# 2_mb_conn.net
KiCad netlist of a schematic drawn in Altium Designer
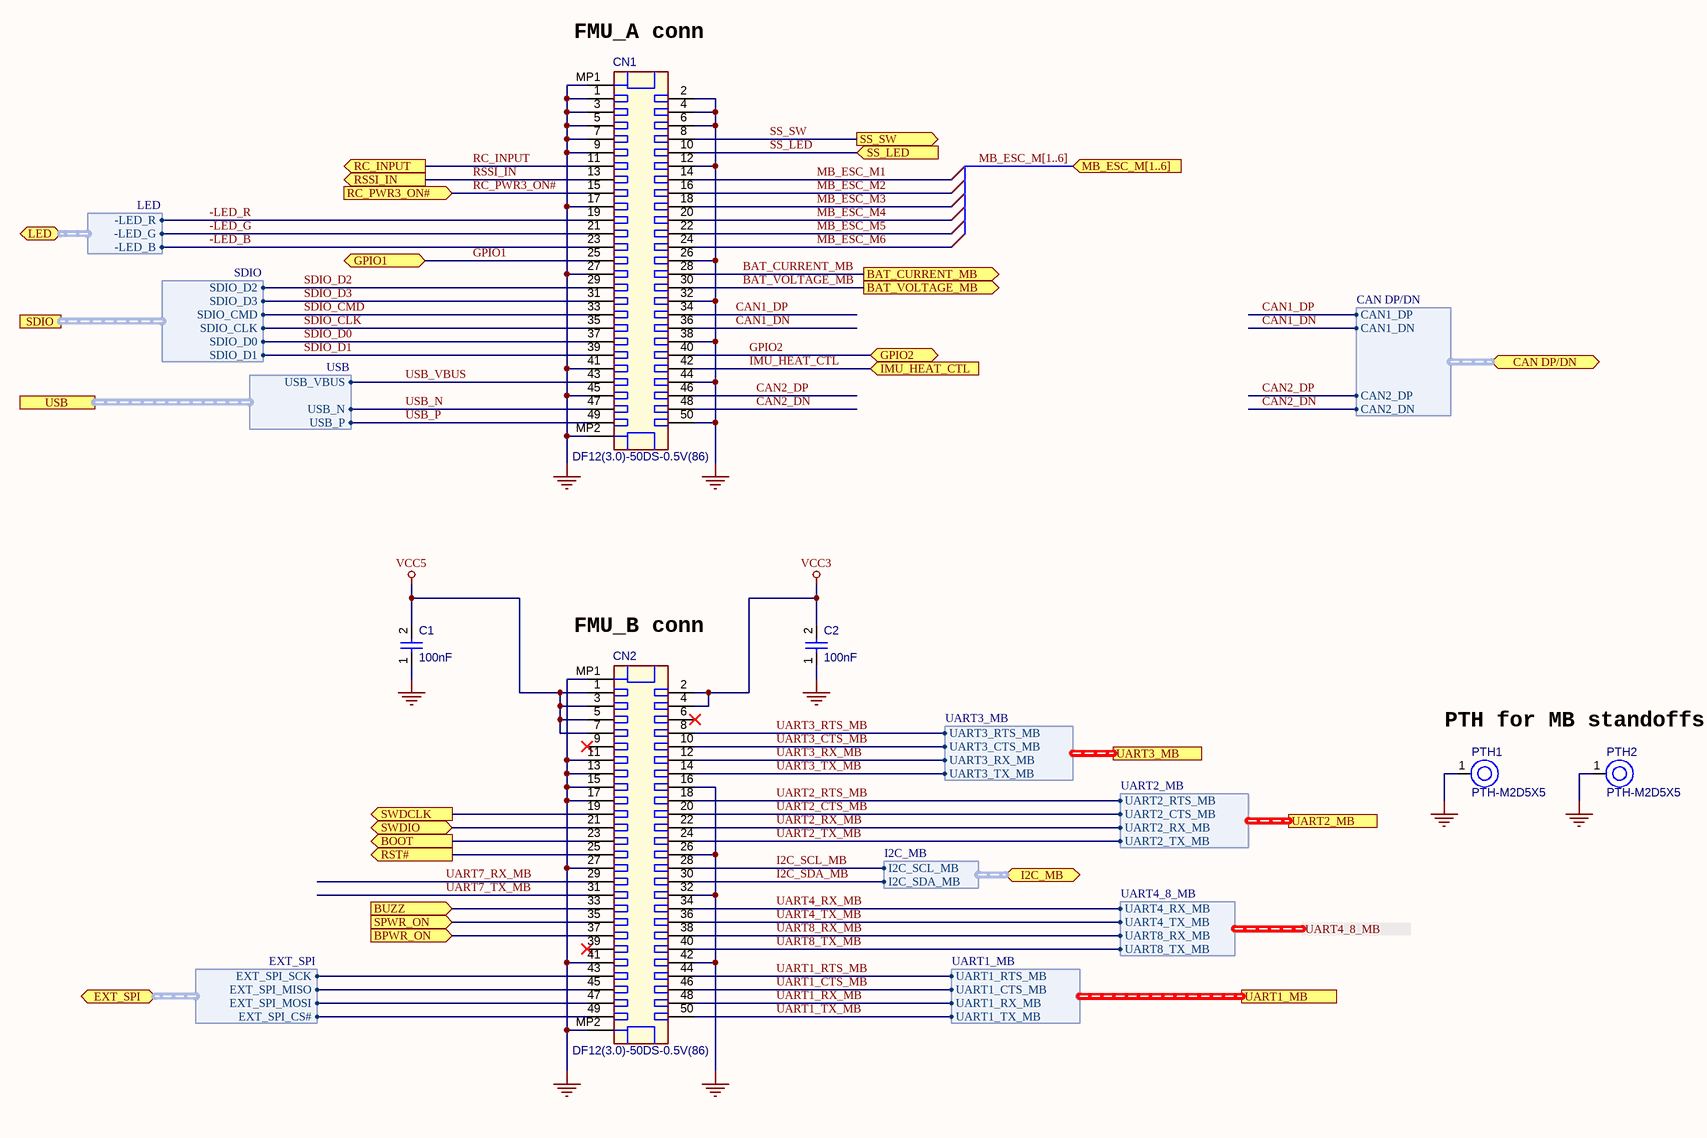
[diagram p0: 2_mb_conn.SchDoc]

(export (version "E")
  (design (tool "Eeschema 10.0.6"))
  (components
    (comp (ref "C1")
      (value "100nF")
      (footprint "CAPC0402(1005)60_L")
      (description "Chip Capacitor, 100nF +/-20%, 10V, 0402, Thickness 0.6 mm")
      (fields (field (name "TOLERANCE") "20%") (field (name "Comment") "Capacitor 100nF +/-20% 10V 0402"))
      (libsource (lib "<Company> Server") (part "CAP-NP-2"))
    )
    (comp (ref "C2")
      (value "100nF")
      (footprint "CAPC0402(1005)60_L")
      (description "Chip Capacitor, 100nF +/-20%, 10V, 0402, Thickness 0.6 mm")
      (fields (field (name "TOLERANCE") "20%") (field (name "Comment") "Capacitor 100nF +/-20% 10V 0402"))
      (libsource (lib "<Company> Server") (part "CAP-NP-2"))
    )
    (comp (ref "CN1")
      (value "DF12(3.0)-50DS-0.5V(86)")
      (footprint "HIRO-DF12(3.0)-50DS-0.5V_V")
      (description "Receptacle Connector, 50 V, 0.3 A, -45 to 125 degC, RoHS, Tape and Reel")
      (libsource (lib "<Company> Server") (part "CMP-00111-4"))
    )
    (comp (ref "CN2")
      (value "DF12(3.0)-50DS-0.5V(86)")
      (footprint "HIRO-DF12(3.0)-50DS-0.5V_V")
      (description "Receptacle Connector, 50 V, 0.3 A, -45 to 125 degC, RoHS, Tape and Reel")
      (libsource (lib "<Company> Server") (part "CMP-00111-4"))
    )
    (comp (ref "PTH1")
      (value "PTH-M2D5X5")
      (footprint "PTH-M2D5X5")
      (description "M2 PTH (2.5mm), 5mm pad")
      (libsource (lib "<Company> Server") (part "CMP-00028-00000-1"))
    )
    (comp (ref "PTH2")
      (value "PTH-M2D5X5")
      (footprint "PTH-M2D5X5")
      (description "M2 PTH (2.5mm), 5mm pad")
      (libsource (lib "<Company> Server") (part "CMP-00028-00000-1"))
    )
  )
  (nets
    (net (code "12") (name "/-LED_B") (class "Default")
      (node (ref "CN1") (pin "23") (pinfunction "23_23") (pintype "passive"))
    )
    (net (code "13") (name "/-LED_G") (class "Default")
      (node (ref "CN1") (pin "21") (pinfunction "21_21") (pintype "passive"))
    )
    (net (code "14") (name "/-LED_R") (class "Default")
      (node (ref "CN1") (pin "19") (pinfunction "19_19") (pintype "passive"))
    )
    (net (code "15") (name "/BAT_CURRENT_MB") (class "Default")
      (node (ref "CN1") (pin "28") (pinfunction "28_28") (pintype "passive"))
    )
    (net (code "16") (name "/BAT_VOLTAGE_MB") (class "Default")
      (node (ref "CN1") (pin "30") (pinfunction "30_30") (pintype "passive"))
    )
    (net (code "17") (name "/BOOT") (class "Default")
      (node (ref "CN2") (pin "23") (pinfunction "23_23") (pintype "passive"))
    )
    (net (code "18") (name "/BPWR_ON") (class "Default")
      (node (ref "CN2") (pin "37") (pinfunction "37_37") (pintype "passive"))
    )
    (net (code "19") (name "/BUZZ") (class "Default")
      (node (ref "CN2") (pin "33") (pinfunction "33_33") (pintype "passive"))
    )
    (net (code "20") (name "/CAN1_DN") (class "Default")
      (node (ref "CN1") (pin "36") (pinfunction "36_36") (pintype "passive"))
    )
    (net (code "21") (name "/CAN1_DP") (class "Default")
      (node (ref "CN1") (pin "34") (pinfunction "34_34") (pintype "passive"))
    )
    (net (code "22") (name "/CAN2_DN") (class "Default")
      (node (ref "CN1") (pin "48") (pinfunction "48_48") (pintype "passive"))
    )
    (net (code "23") (name "/CAN2_DP") (class "Default")
      (node (ref "CN1") (pin "46") (pinfunction "46_46") (pintype "passive"))
    )
    (net (code "24") (name "/EXT_SPI_CS#") (class "Default")
      (node (ref "CN2") (pin "49") (pinfunction "49_49") (pintype "passive"))
    )
    (net (code "25") (name "/EXT_SPI_MISO") (class "Default")
      (node (ref "CN2") (pin "45") (pinfunction "45_45") (pintype "passive"))
    )
    (net (code "26") (name "/EXT_SPI_MOSI") (class "Default")
      (node (ref "CN2") (pin "47") (pinfunction "47_47") (pintype "passive"))
    )
    (net (code "27") (name "/EXT_SPI_SCK") (class "Default")
      (node (ref "CN2") (pin "43") (pinfunction "43_43") (pintype "passive"))
    )
    (net (code "28") (name "/GPIO1") (class "Default")
      (node (ref "CN1") (pin "25") (pinfunction "25_25") (pintype "passive"))
    )
    (net (code "29") (name "/GPIO2") (class "Default")
      (node (ref "CN1") (pin "40") (pinfunction "40_40") (pintype "passive"))
    )
    (net (code "30") (name "/I2C_SCL_MB") (class "Default")
      (node (ref "CN2") (pin "28") (pinfunction "28_28") (pintype "passive"))
    )
    (net (code "31") (name "/I2C_SDA_MB") (class "Default")
      (node (ref "CN2") (pin "30") (pinfunction "30_30") (pintype "passive"))
    )
    (net (code "32") (name "/IMU_HEAT_CTL") (class "Default")
      (node (ref "CN1") (pin "42") (pinfunction "42_42") (pintype "passive"))
    )
    (net (code "33") (name "/MB_ESC_M1") (class "Default")
      (node (ref "CN1") (pin "14") (pinfunction "14_14") (pintype "passive"))
    )
    (net (code "34") (name "/MB_ESC_M2") (class "Default")
      (node (ref "CN1") (pin "16") (pinfunction "16_16") (pintype "passive"))
    )
    (net (code "35") (name "/MB_ESC_M3") (class "Default")
      (node (ref "CN1") (pin "18") (pinfunction "18_18") (pintype "passive"))
    )
    (net (code "36") (name "/MB_ESC_M4") (class "Default")
      (node (ref "CN1") (pin "20") (pinfunction "20_20") (pintype "passive"))
    )
    (net (code "37") (name "/MB_ESC_M5") (class "Default")
      (node (ref "CN1") (pin "22") (pinfunction "22_22") (pintype "passive"))
    )
    (net (code "38") (name "/MB_ESC_M6") (class "Default")
      (node (ref "CN1") (pin "24") (pinfunction "24_24") (pintype "passive"))
    )
    (net (code "40") (name "/RC_INPUT") (class "Default")
      (node (ref "CN1") (pin "11") (pinfunction "11_11") (pintype "passive"))
    )
    (net (code "41") (name "/RC_PWR3_ON#") (class "Default")
      (node (ref "CN1") (pin "15") (pinfunction "15_15") (pintype "passive"))
    )
    (net (code "42") (name "/RSSI_IN") (class "Default")
      (node (ref "CN1") (pin "13") (pinfunction "13_13") (pintype "passive"))
    )
    (net (code "43") (name "/RST#") (class "Default")
      (node (ref "CN2") (pin "25") (pinfunction "25_25") (pintype "passive"))
    )
    (net (code "44") (name "/SDIO_CLK") (class "Default")
      (node (ref "CN1") (pin "35") (pinfunction "35_35") (pintype "passive"))
    )
    (net (code "45") (name "/SDIO_CMD") (class "Default")
      (node (ref "CN1") (pin "33") (pinfunction "33_33") (pintype "passive"))
    )
    (net (code "46") (name "/SDIO_D0") (class "Default")
      (node (ref "CN1") (pin "37") (pinfunction "37_37") (pintype "passive"))
    )
    (net (code "47") (name "/SDIO_D1") (class "Default")
      (node (ref "CN1") (pin "39") (pinfunction "39_39") (pintype "passive"))
    )
    (net (code "48") (name "/SDIO_D2") (class "Default")
      (node (ref "CN1") (pin "29") (pinfunction "29_29") (pintype "passive"))
    )
    (net (code "49") (name "/SDIO_D3") (class "Default")
      (node (ref "CN1") (pin "31") (pinfunction "31_31") (pintype "passive"))
    )
    (net (code "50") (name "/SPWR_ON") (class "Default")
      (node (ref "CN2") (pin "35") (pinfunction "35_35") (pintype "passive"))
    )
    (net (code "51") (name "/SS_LED") (class "Default")
      (node (ref "CN1") (pin "10") (pinfunction "10_10") (pintype "passive"))
    )
    (net (code "52") (name "/SS_SW") (class "Default")
      (node (ref "CN1") (pin "8") (pinfunction "8_8") (pintype "passive"))
    )
    (net (code "53") (name "/SWDCLK") (class "Default")
      (node (ref "CN2") (pin "19") (pinfunction "19_19") (pintype "passive"))
    )
    (net (code "54") (name "/SWDIO") (class "Default")
      (node (ref "CN2") (pin "21") (pinfunction "21_21") (pintype "passive"))
    )
    (net (code "55") (name "/UART1_CTS_MB") (class "Default")
      (node (ref "CN2") (pin "46") (pinfunction "46_46") (pintype "passive"))
    )
    (net (code "56") (name "/UART1_RTS_MB") (class "Default")
      (node (ref "CN2") (pin "44") (pinfunction "44_44") (pintype "passive"))
    )
    (net (code "57") (name "/UART1_RX_MB") (class "Default")
      (node (ref "CN2") (pin "48") (pinfunction "48_48") (pintype "passive"))
    )
    (net (code "58") (name "/UART1_TX_MB") (class "Default")
      (node (ref "CN2") (pin "50") (pinfunction "50_50") (pintype "passive"))
    )
    (net (code "59") (name "/UART2_CTS_MB") (class "Default")
      (node (ref "CN2") (pin "20") (pinfunction "20_20") (pintype "passive"))
    )
    (net (code "60") (name "/UART2_RTS_MB") (class "Default")
      (node (ref "CN2") (pin "18") (pinfunction "18_18") (pintype "passive"))
    )
    (net (code "61") (name "/UART2_RX_MB") (class "Default")
      (node (ref "CN2") (pin "22") (pinfunction "22_22") (pintype "passive"))
    )
    (net (code "62") (name "/UART2_TX_MB") (class "Default")
      (node (ref "CN2") (pin "24") (pinfunction "24_24") (pintype "passive"))
    )
    (net (code "63") (name "/UART3_CTS_MB") (class "Default")
      (node (ref "CN2") (pin "10") (pinfunction "10_10") (pintype "passive"))
    )
    (net (code "64") (name "/UART3_RTS_MB") (class "Default")
      (node (ref "CN2") (pin "8") (pinfunction "8_8") (pintype "passive"))
    )
    (net (code "65") (name "/UART3_RX_MB") (class "Default")
      (node (ref "CN2") (pin "12") (pinfunction "12_12") (pintype "passive"))
    )
    (net (code "66") (name "/UART3_TX_MB") (class "Default")
      (node (ref "CN2") (pin "14") (pinfunction "14_14") (pintype "passive"))
    )
    (net (code "67") (name "/UART4_RX_MB") (class "Default")
      (node (ref "CN2") (pin "34") (pinfunction "34_34") (pintype "passive"))
    )
    (net (code "68") (name "/UART4_TX_MB") (class "Default")
      (node (ref "CN2") (pin "36") (pinfunction "36_36") (pintype "passive"))
    )
    (net (code "69") (name "/UART7_RX_MB") (class "Default")
      (node (ref "CN2") (pin "29") (pinfunction "29_29") (pintype "passive"))
    )
    (net (code "70") (name "/UART7_TX_MB") (class "Default")
      (node (ref "CN2") (pin "31") (pinfunction "31_31") (pintype "passive"))
    )
    (net (code "71") (name "/UART8_RX_MB") (class "Default")
      (node (ref "CN2") (pin "38") (pinfunction "38_38") (pintype "passive"))
    )
    (net (code "72") (name "/UART8_TX_MB") (class "Default")
      (node (ref "CN2") (pin "40") (pinfunction "40_40") (pintype "passive"))
    )
    (net (code "73") (name "/USB_N") (class "Default")
      (node (ref "CN1") (pin "47") (pinfunction "47_47") (pintype "passive"))
    )
    (net (code "74") (name "/USB_P") (class "Default")
      (node (ref "CN1") (pin "49") (pinfunction "49_49") (pintype "passive"))
    )
    (net (code "75") (name "/USB_VBUS") (class "Default")
      (node (ref "CN1") (pin "43") (pinfunction "43_43") (pintype "passive"))
    )
    (net (code "86") (name "GND") (class "Default")
      (node (ref "C1") (pin "1") (pinfunction "1_1") (pintype "passive"))
      (node (ref "C2") (pin "1") (pinfunction "1_1") (pintype "passive"))
      (node (ref "CN1") (pin "1") (pinfunction "1_1") (pintype "passive"))
      (node (ref "CN1") (pin "12") (pinfunction "12_12") (pintype "passive"))
      (node (ref "CN1") (pin "17") (pinfunction "17_17") (pintype "passive"))
      (node (ref "CN1") (pin "2") (pinfunction "2_2") (pintype "passive"))
      (node (ref "CN1") (pin "26") (pinfunction "26_26") (pintype "passive"))
      (node (ref "CN1") (pin "27") (pinfunction "27_27") (pintype "passive"))
      (node (ref "CN1") (pin "3") (pinfunction "3_3") (pintype "passive"))
      (node (ref "CN1") (pin "32") (pinfunction "32_32") (pintype "passive"))
      (node (ref "CN1") (pin "38") (pinfunction "38_38") (pintype "passive"))
      (node (ref "CN1") (pin "4") (pinfunction "4_4") (pintype "passive"))
      (node (ref "CN1") (pin "41") (pinfunction "41_41") (pintype "passive"))
      (node (ref "CN1") (pin "44") (pinfunction "44_44") (pintype "passive"))
      (node (ref "CN1") (pin "45") (pinfunction "45_45") (pintype "passive"))
      (node (ref "CN1") (pin "5") (pinfunction "5_5") (pintype "passive"))
      (node (ref "CN1") (pin "50") (pinfunction "50_50") (pintype "passive"))
      (node (ref "CN1") (pin "6") (pinfunction "6_6") (pintype "passive"))
      (node (ref "CN1") (pin "7") (pinfunction "7_7") (pintype "passive"))
      (node (ref "CN1") (pin "9") (pinfunction "9_9") (pintype "passive"))
      (node (ref "CN1") (pin "MP1") (pinfunction "MP1_MP1") (pintype "passive"))
      (node (ref "CN1") (pin "MP2") (pinfunction "MP2_MP2") (pintype "passive"))
      (node (ref "CN2") (pin "11") (pinfunction "11_11") (pintype "passive"))
      (node (ref "CN2") (pin "13") (pinfunction "13_13") (pintype "passive"))
      (node (ref "CN2") (pin "15") (pinfunction "15_15") (pintype "passive"))
      (node (ref "CN2") (pin "16") (pinfunction "16_16") (pintype "passive"))
      (node (ref "CN2") (pin "17") (pinfunction "17_17") (pintype "passive"))
      (node (ref "CN2") (pin "26") (pinfunction "26_26") (pintype "passive"))
      (node (ref "CN2") (pin "27") (pinfunction "27_27") (pintype "passive"))
      (node (ref "CN2") (pin "32") (pinfunction "32_32") (pintype "passive"))
      (node (ref "CN2") (pin "41") (pinfunction "41_41") (pintype "passive"))
      (node (ref "CN2") (pin "42") (pinfunction "42_42") (pintype "passive"))
      (node (ref "CN2") (pin "MP1") (pinfunction "MP1_MP1") (pintype "passive"))
      (node (ref "CN2") (pin "MP2") (pinfunction "MP2_MP2") (pintype "passive"))
      (node (ref "PTH1") (pin "1") (pinfunction "H1_1") (pintype "passive"))
      (node (ref "PTH2") (pin "1") (pinfunction "H1_1") (pintype "passive"))
    )
    (net (code "87") (name "VCC3") (class "Default")
      (node (ref "C2") (pin "2") (pinfunction "2_2") (pintype "passive"))
      (node (ref "CN2") (pin "2") (pinfunction "2_2") (pintype "passive"))
      (node (ref "CN2") (pin "4") (pinfunction "4_4") (pintype "passive"))
    )
    (net (code "88") (name "VCC5") (class "Default")
      (node (ref "C1") (pin "2") (pinfunction "2_2") (pintype "passive"))
      (node (ref "CN2") (pin "1") (pinfunction "1_1") (pintype "passive"))
      (node (ref "CN2") (pin "3") (pinfunction "3_3") (pintype "passive"))
      (node (ref "CN2") (pin "5") (pinfunction "5_5") (pintype "passive"))
      (node (ref "CN2") (pin "7") (pinfunction "7_7") (pintype "passive"))
    )
    (net (code "89") (name "unconnected-(CN2-Pad6)") (class "Default")
      (node (ref "CN2") (pin "6") (pinfunction "6_6") (pintype "passive+no_connect"))
    )
    (net (code "90") (name "unconnected-(CN2-Pad9)") (class "Default")
      (node (ref "CN2") (pin "9") (pinfunction "9_9") (pintype "passive+no_connect"))
    )
    (net (code "91") (name "unconnected-(CN2-Pad39)") (class "Default")
      (node (ref "CN2") (pin "39") (pinfunction "39_39") (pintype "passive+no_connect"))
    )
  )
)
